# SENSORS.net
KiCad netlist of a schematic drawn in Altium Designer
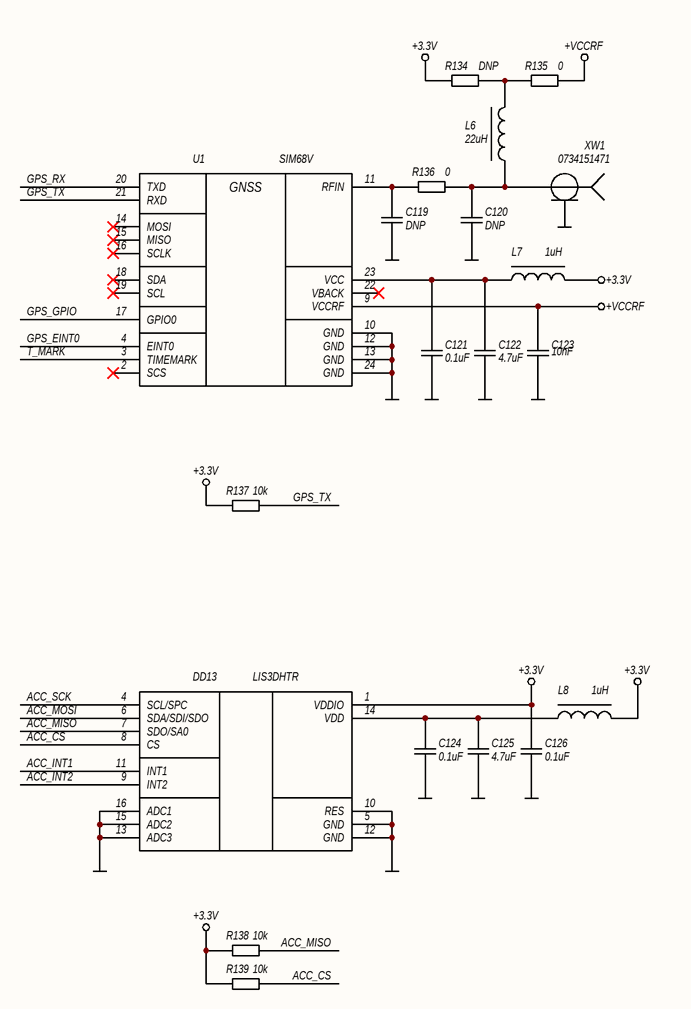
[diagram p0: SENSORS.SchDoc]

(export (version "E")
  (design (tool "Eeschema 10.0.6"))
  (components
    (comp (ref "C119")
      (value "DNP")
      (footprint "C0603N")
      (description "Конденсатор")
      (libsource (lib "Components Library") (part "CAP_FIXED"))
    )
    (comp (ref "C120")
      (value "DNP")
      (footprint "C0603N")
      (description "Конденсатор")
      (libsource (lib "Components Library") (part "CAP_FIXED"))
    )
    (comp (ref "C121")
      (value "0.1uF")
      (footprint "C0603N")
      (description "Конденсатор")
      (libsource (lib "Components Library") (part "CAP_FIXED"))
    )
    (comp (ref "C122")
      (value "4.7uF")
      (footprint "C0603N")
      (description "Конденсатор")
      (libsource (lib "Components Library") (part "CAP_FIXED"))
    )
    (comp (ref "C123")
      (value "10nF")
      (footprint "C0603N")
      (description "Конденсатор")
      (libsource (lib "Components Library") (part "CAP_FIXED"))
    )
    (comp (ref "C124")
      (value "0.1uF")
      (footprint "C0603N")
      (description "Конденсатор")
      (libsource (lib "Components Library") (part "CAP_FIXED"))
    )
    (comp (ref "C125")
      (value "4.7uF")
      (footprint "C0603N")
      (description "Конденсатор")
      (libsource (lib "Components Library") (part "CAP_FIXED"))
    )
    (comp (ref "C126")
      (value "0.1uF")
      (footprint "C0603N")
      (description "Конденсатор")
      (libsource (lib "Components Library") (part "CAP_FIXED"))
    )
    (comp (ref "DD13")
      (value "LIS3DHTR")
      (footprint "LGA-16")
      (description "Микросхема MEMS акселерометр")
      (libsource (lib "Components Library") (part "LIS3DH"))
    )
    (comp (ref "L6")
      (value "22uH")
      (footprint "NLCV32-EF")
      (description "Дроссель с магнитопроводом")
      (libsource (lib "Components Library") (part "IND_CORE"))
    )
    (comp (ref "L7")
      (value "1uH")
      (footprint "NLCV32-EF")
      (description "Дроссель с магнитопроводом")
      (libsource (lib "Components Library") (part "IND_CORE"))
    )
    (comp (ref "L8")
      (value "1uH")
      (footprint "NLCV32-EF")
      (description "Дроссель с магнитопроводом")
      (libsource (lib "Components Library") (part "IND_CORE"))
    )
    (comp (ref "R134")
      (value "DNP")
      (footprint "R0603N")
      (description "Резистор")
      (libsource (lib "Components Library") (part "RES_FIXED"))
    )
    (comp (ref "R135")
      (value "0")
      (footprint "R0603N")
      (description "Резистор")
      (libsource (lib "") (part "RES_FIXED_1"))
    )
    (comp (ref "R136")
      (value "0")
      (footprint "R0603N")
      (description "Резистор")
      (libsource (lib "Components Library") (part "RES_FIXED"))
    )
    (comp (ref "R137")
      (value "10k")
      (footprint "R0603N")
      (description "Резистор")
      (libsource (lib "Components Library") (part "RES_FIXED"))
    )
    (comp (ref "R138")
      (value "10k")
      (footprint "R0603N")
      (description "Резистор")
      (libsource (lib "Components Library") (part "RES_FIXED"))
    )
    (comp (ref "R139")
      (value "10k")
      (footprint "R0603N")
      (description "Резистор")
      (libsource (lib "Components Library") (part "RES_FIXED"))
    )
    (comp (ref "U1")
      (value "SIM68V")
      (footprint "SIM68V")
      (description "Модуль GNSS приемника")
      (libsource (lib "Components Library") (part "SIM68V"))
    )
    (comp (ref "XW1")
      (value "0734151471")
      (footprint "0734151471")
      (description "ВЧ соединитель")
      (libsource (lib "Components Library") (part "Connector Coax F"))
    )
  )
  (nets
    (net (code "1") (name "+3.3V") (class "Default")
      (node (ref "C126") (pin "2") (pinfunction "2_2") (pintype "passive"))
      (node (ref "DD13") (pin "1") (pinfunction "VDDIO_1") (pintype "power_in"))
      (node (ref "L7") (pin "2") (pinfunction "2_2") (pintype "passive"))
      (node (ref "L8") (pin "2") (pinfunction "2_2") (pintype "passive"))
      (node (ref "R134") (pin "2") (pinfunction "2_2") (pintype "passive"))
      (node (ref "R137") (pin "2") (pinfunction "2_2") (pintype "passive"))
      (node (ref "R138") (pin "2") (pinfunction "2_2") (pintype "passive"))
      (node (ref "R139") (pin "2") (pinfunction "2_2") (pintype "passive"))
    )
    (net (code "2") (name "+VCCRF") (class "Default")
      (node (ref "C123") (pin "1") (pinfunction "1_1") (pintype "passive"))
      (node (ref "R135") (pin "2") (pinfunction "2_2") (pintype "passive"))
      (node (ref "U1") (pin "9") (pinfunction "VCCRF_9") (pintype "power_in"))
    )
    (net (code "3") (name "/ACC_CS") (class "Default")
      (node (ref "DD13") (pin "8") (pinfunction "CS_8") (pintype "power_in"))
      (node (ref "R139") (pin "1") (pinfunction "1_1") (pintype "passive"))
    )
    (net (code "4") (name "/ACC_INT1") (class "Default")
      (node (ref "DD13") (pin "11") (pinfunction "INT1_11") (pintype "power_in"))
    )
    (net (code "5") (name "/ACC_INT2") (class "Default")
      (node (ref "DD13") (pin "9") (pinfunction "INT2_9") (pintype "power_in"))
    )
    (net (code "6") (name "/ACC_MISO") (class "Default")
      (node (ref "DD13") (pin "7") (pinfunction "SDO/SA0_7") (pintype "power_in"))
      (node (ref "R138") (pin "1") (pinfunction "1_1") (pintype "passive"))
    )
    (net (code "7") (name "/ACC_MOSI") (class "Default")
      (node (ref "DD13") (pin "6") (pinfunction "SDA/SDI/SDO_6") (pintype "power_in"))
    )
    (net (code "8") (name "/ACC_SCK") (class "Default")
      (node (ref "DD13") (pin "4") (pinfunction "SCL/SPC_4") (pintype "power_in"))
    )
    (net (code "9") (name "/GPS_EINT0") (class "Default")
      (node (ref "U1") (pin "4") (pinfunction "EINT0_4") (pintype "power_in"))
    )
    (net (code "10") (name "/GPS_GPIO") (class "Default")
      (node (ref "U1") (pin "17") (pinfunction "GPIO0_17") (pintype "power_in"))
    )
    (net (code "11") (name "/GPS_RX") (class "Default")
      (node (ref "U1") (pin "20") (pinfunction "TXD_20") (pintype "power_in"))
    )
    (net (code "12") (name "/GPS_TX") (class "Default")
      (node (ref "R137") (pin "1") (pinfunction "1_1") (pintype "passive"))
      (node (ref "U1") (pin "21") (pinfunction "RXD_21") (pintype "power_in"))
    )
    (net (code "13") (name "/T_MARK") (class "Default")
      (node (ref "U1") (pin "3") (pinfunction "TIMEMARK_3") (pintype "power_in"))
    )
    (net (code "14") (name "GND") (class "Default")
      (node (ref "C119") (pin "1") (pinfunction "1_1") (pintype "passive"))
      (node (ref "C120") (pin "1") (pinfunction "1_1") (pintype "passive"))
      (node (ref "C121") (pin "1") (pinfunction "1_1") (pintype "passive"))
      (node (ref "C122") (pin "1") (pinfunction "1_1") (pintype "passive"))
      (node (ref "C123") (pin "2") (pinfunction "2_2") (pintype "passive"))
      (node (ref "C124") (pin "1") (pinfunction "1_1") (pintype "passive"))
      (node (ref "C125") (pin "1") (pinfunction "1_1") (pintype "passive"))
      (node (ref "C126") (pin "1") (pinfunction "1_1") (pintype "passive"))
      (node (ref "DD13") (pin "10") (pinfunction "RES_10") (pintype "power_in"))
      (node (ref "DD13") (pin "12") (pinfunction "GND_12") (pintype "power_in"))
      (node (ref "DD13") (pin "13") (pinfunction "ADC3_13") (pintype "power_in"))
      (node (ref "DD13") (pin "15") (pinfunction "ADC2_15") (pintype "power_in"))
      (node (ref "DD13") (pin "16") (pinfunction "ADC1_16") (pintype "power_in"))
      (node (ref "DD13") (pin "5") (pinfunction "GND_5") (pintype "power_in"))
      (node (ref "U1") (pin "10") (pinfunction "GND_10") (pintype "power_in"))
      (node (ref "U1") (pin "12") (pinfunction "GND_12") (pintype "power_in"))
      (node (ref "U1") (pin "13") (pinfunction "GND_13") (pintype "power_in"))
      (node (ref "U1") (pin "24") (pinfunction "GND_24") (pintype "power_in"))
      (node (ref "XW1") (pin "2") (pinfunction "GND_2") (pintype "passive"))
    )
    (net (code "15") (name "Net-(C120-Pad2)") (class "Default")
      (node (ref "C120") (pin "2") (pinfunction "2_2") (pintype "passive"))
      (node (ref "L6") (pin "1") (pinfunction "1_1") (pintype "passive"))
      (node (ref "R136") (pin "1") (pinfunction "1_1") (pintype "passive"))
      (node (ref "XW1") (pin "1") (pintype "passive"))
    )
    (net (code "16") (name "Net-(DD13-VDD)") (class "Default")
      (node (ref "C124") (pin "2") (pinfunction "2_2") (pintype "passive"))
      (node (ref "C125") (pin "2") (pinfunction "2_2") (pintype "passive"))
      (node (ref "DD13") (pin "14") (pinfunction "VDD_14") (pintype "power_in"))
      (node (ref "L8") (pin "1") (pinfunction "1_1") (pintype "passive"))
    )
    (net (code "17") (name "Net-(L6-Pad2)") (class "Default")
      (node (ref "L6") (pin "2") (pinfunction "2_2") (pintype "passive"))
      (node (ref "R134") (pin "1") (pinfunction "1_1") (pintype "passive"))
      (node (ref "R135") (pin "1") (pinfunction "1_1") (pintype "passive"))
    )
    (net (code "18") (name "Net-(U1-RFIN)") (class "Default")
      (node (ref "C119") (pin "2") (pinfunction "2_2") (pintype "passive"))
      (node (ref "R136") (pin "2") (pinfunction "2_2") (pintype "passive"))
      (node (ref "U1") (pin "11") (pinfunction "RFIN_11") (pintype "power_in"))
    )
    (net (code "19") (name "Net-(U1-VCC)") (class "Default")
      (node (ref "C121") (pin "2") (pinfunction "2_2") (pintype "passive"))
      (node (ref "C122") (pin "2") (pinfunction "2_2") (pintype "passive"))
      (node (ref "L7") (pin "1") (pinfunction "1_1") (pintype "passive"))
      (node (ref "U1") (pin "23") (pinfunction "VCC_23") (pintype "power_in"))
    )
    (net (code "20") (name "unconnected-(U1-MISO-Pad15)") (class "Default")
      (node (ref "U1") (pin "15") (pinfunction "MISO_15") (pintype "power_in+no_connect"))
    )
    (net (code "21") (name "unconnected-(U1-MOSI-Pad14)") (class "Default")
      (node (ref "U1") (pin "14") (pinfunction "MOSI_14") (pintype "power_in+no_connect"))
    )
    (net (code "22") (name "unconnected-(U1-SCL-Pad19)") (class "Default")
      (node (ref "U1") (pin "19") (pinfunction "SCL_19") (pintype "power_in+no_connect"))
    )
    (net (code "23") (name "unconnected-(U1-SCLK-Pad16)") (class "Default")
      (node (ref "U1") (pin "16") (pinfunction "SCLK_16") (pintype "power_in+no_connect"))
    )
    (net (code "24") (name "unconnected-(U1-SCS-Pad2)") (class "Default")
      (node (ref "U1") (pin "2") (pinfunction "SCS_2") (pintype "power_in+no_connect"))
    )
    (net (code "25") (name "unconnected-(U1-SDA-Pad18)") (class "Default")
      (node (ref "U1") (pin "18") (pinfunction "SDA_18") (pintype "power_in+no_connect"))
    )
    (net (code "26") (name "unconnected-(U1-VBACK-Pad22)") (class "Default")
      (node (ref "U1") (pin "22") (pinfunction "VBACK_22") (pintype "power_in+no_connect"))
    )
  )
)
